# main.net
KiCad netlist of a schematic drawn in Altium Designer
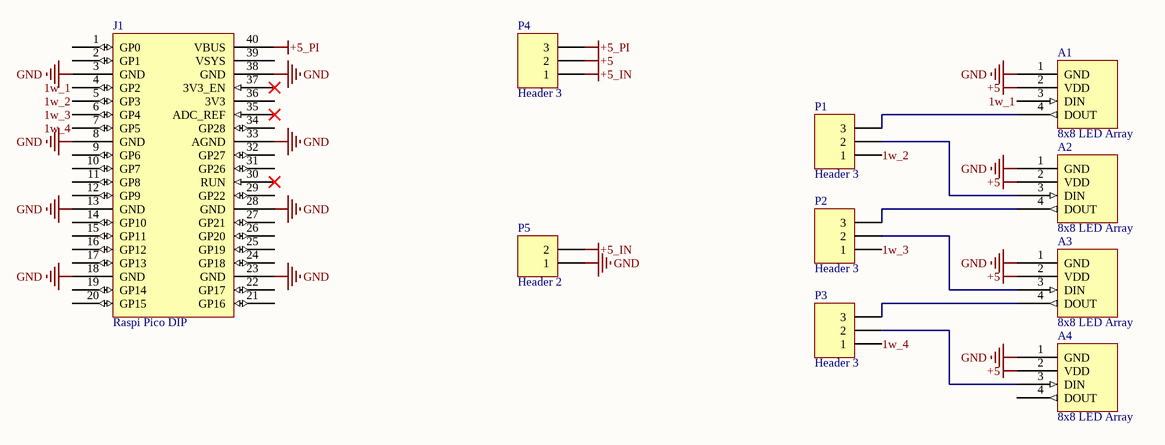
[diagram p0: main.SchDoc]

(export (version "E")
  (design (tool "Eeschema 10.0.6"))
  (components
    (comp (ref "A1")
      (value "8x8 LED Array")
      (footprint "12x12 SK6805 Matrix")
      (libsource (lib "SchmittLib") (part "12x12 SK6805 Array"))
    )
    (comp (ref "A2")
      (value "8x8 LED Array")
      (footprint "12x12 SK6805 Matrix")
      (libsource (lib "SchmittLib") (part "12x12 SK6805 Array"))
    )
    (comp (ref "A3")
      (value "8x8 LED Array")
      (footprint "12x12 SK6805 Matrix")
      (libsource (lib "SchmittLib") (part "12x12 SK6805 Array"))
    )
    (comp (ref "A4")
      (value "8x8 LED Array")
      (footprint "12x12 SK6805 Matrix")
      (libsource (lib "SchmittLib") (part "12x12 SK6805 Array"))
    )
    (comp (ref "J1")
      (value "Raspi Pico DIP")
      (footprint "Raspi Pico DIP")
      (libsource (lib "SchmittLib") (part "Raspi Pico DIP"))
    )
    (comp (ref "P1")
      (value "Header 3")
      (footprint "HDR1X3")
      (description "Header, 3-Pin")
      (fields (field (name "PUBLISHER") "Altium Limited"))
      (libsource (lib "Miscellaneous Connectors") (part "Header 3"))
    )
    (comp (ref "P2")
      (value "Header 3")
      (footprint "HDR1X3")
      (description "Header, 3-Pin")
      (fields (field (name "PUBLISHER") "Altium Limited"))
      (libsource (lib "Miscellaneous Connectors") (part "Header 3"))
    )
    (comp (ref "P3")
      (value "Header 3")
      (footprint "HDR1X3")
      (description "Header, 3-Pin")
      (fields (field (name "PUBLISHER") "Altium Limited"))
      (libsource (lib "Miscellaneous Connectors") (part "Header 3"))
    )
    (comp (ref "P4")
      (value "Header 3")
      (footprint "HDR1X3")
      (description "Header, 3-Pin")
      (fields (field (name "PUBLISHER") "Altium Limited"))
      (libsource (lib "Miscellaneous Connectors") (part "Header 3"))
    )
    (comp (ref "P5")
      (value "Header 2")
      (footprint "HDR1X2")
      (description "Header, 2-Pin")
      (fields (field (name "PUBLISHER") "Altium Limited"))
      (libsource (lib "Miscellaneous Connectors") (part "Header 2"))
    )
  )
  (nets
    (net (code "1") (name "+5") (class "Default")
      (node (ref "A1") (pin "2") (pinfunction "VDD_2") (pintype "power_in"))
      (node (ref "A2") (pin "2") (pinfunction "VDD_2") (pintype "power_in"))
      (node (ref "A3") (pin "2") (pinfunction "VDD_2") (pintype "power_in"))
      (node (ref "A4") (pin "2") (pinfunction "VDD_2") (pintype "power_in"))
      (node (ref "P4") (pin "2") (pinfunction "2_2") (pintype "passive"))
    )
    (net (code "2") (name "+5_IN") (class "Default")
      (node (ref "P4") (pin "1") (pinfunction "1_1") (pintype "passive"))
      (node (ref "P5") (pin "2") (pinfunction "2_2") (pintype "passive"))
    )
    (net (code "3") (name "+5_PI") (class "Default")
      (node (ref "J1") (pin "40") (pinfunction "VBUS_40") (pintype "power_in"))
      (node (ref "P4") (pin "3") (pinfunction "3_3") (pintype "passive"))
    )
    (net (code "4") (name "/1w_1") (class "Default")
      (node (ref "A1") (pin "3") (pinfunction "DIN_3") (pintype "input"))
      (node (ref "J1") (pin "4") (pinfunction "GP2_4") (pintype "bidirectional"))
    )
    (net (code "5") (name "/1w_2") (class "Default")
      (node (ref "J1") (pin "5") (pinfunction "GP3_5") (pintype "bidirectional"))
      (node (ref "P1") (pin "1") (pinfunction "1_1") (pintype "passive"))
    )
    (net (code "6") (name "/1w_3") (class "Default")
      (node (ref "J1") (pin "6") (pinfunction "GP4_6") (pintype "bidirectional"))
      (node (ref "P2") (pin "1") (pinfunction "1_1") (pintype "passive"))
    )
    (net (code "7") (name "/1w_4") (class "Default")
      (node (ref "J1") (pin "7") (pinfunction "GP5_7") (pintype "bidirectional"))
      (node (ref "P3") (pin "1") (pinfunction "1_1") (pintype "passive"))
    )
    (net (code "8") (name "GND") (class "Default")
      (node (ref "A1") (pin "1") (pinfunction "GND_1") (pintype "power_in"))
      (node (ref "A2") (pin "1") (pinfunction "GND_1") (pintype "power_in"))
      (node (ref "A3") (pin "1") (pinfunction "GND_1") (pintype "power_in"))
      (node (ref "A4") (pin "1") (pinfunction "GND_1") (pintype "power_in"))
      (node (ref "J1") (pin "13") (pinfunction "GND_13") (pintype "power_in"))
      (node (ref "J1") (pin "18") (pinfunction "GND_18") (pintype "power_in"))
      (node (ref "J1") (pin "23") (pinfunction "GND_23") (pintype "power_in"))
      (node (ref "J1") (pin "28") (pinfunction "GND_28") (pintype "power_in"))
      (node (ref "J1") (pin "3") (pinfunction "GND_3") (pintype "power_in"))
      (node (ref "J1") (pin "33") (pinfunction "AGND_33") (pintype "power_in"))
      (node (ref "J1") (pin "38") (pinfunction "GND_38") (pintype "power_in"))
      (node (ref "J1") (pin "8") (pinfunction "GND_8") (pintype "power_in"))
      (node (ref "P5") (pin "1") (pinfunction "1_1") (pintype "passive"))
    )
    (net (code "9") (name "Net-(A1-DOUT)") (class "Default")
      (node (ref "A1") (pin "4") (pinfunction "DOUT_4") (pintype "output"))
      (node (ref "P1") (pin "3") (pinfunction "3_3") (pintype "passive"))
    )
    (net (code "10") (name "Net-(A2-DIN)") (class "Default")
      (node (ref "A2") (pin "3") (pinfunction "DIN_3") (pintype "input"))
      (node (ref "P1") (pin "2") (pinfunction "2_2") (pintype "passive"))
    )
    (net (code "11") (name "Net-(A2-DOUT)") (class "Default")
      (node (ref "A2") (pin "4") (pinfunction "DOUT_4") (pintype "output"))
      (node (ref "P2") (pin "3") (pinfunction "3_3") (pintype "passive"))
    )
    (net (code "12") (name "Net-(A3-DIN)") (class "Default")
      (node (ref "A3") (pin "3") (pinfunction "DIN_3") (pintype "input"))
      (node (ref "P2") (pin "2") (pinfunction "2_2") (pintype "passive"))
    )
    (net (code "13") (name "Net-(A3-DOUT)") (class "Default")
      (node (ref "A3") (pin "4") (pinfunction "DOUT_4") (pintype "output"))
      (node (ref "P3") (pin "3") (pinfunction "3_3") (pintype "passive"))
    )
    (net (code "14") (name "Net-(A4-DIN)") (class "Default")
      (node (ref "A4") (pin "3") (pinfunction "DIN_3") (pintype "input"))
      (node (ref "P3") (pin "2") (pinfunction "2_2") (pintype "passive"))
    )
    (net (code "15") (name "unconnected-(A4-DOUT-Pad4)") (class "Default")
      (node (ref "A4") (pin "4") (pinfunction "DOUT_4") (pintype "output"))
    )
    (net (code "16") (name "unconnected-(J1-3V3-Pad36)") (class "Default")
      (node (ref "J1") (pin "36") (pinfunction "3V3_36") (pintype "power_in"))
    )
    (net (code "17") (name "unconnected-(J1-3V3_EN-Pad37)") (class "Default")
      (node (ref "J1") (pin "37") (pinfunction "3V3_EN_37") (pintype "input+no_connect"))
    )
    (net (code "18") (name "unconnected-(J1-ADC_REF-Pad35)") (class "Default")
      (node (ref "J1") (pin "35") (pinfunction "ADC_REF_35") (pintype "input+no_connect"))
    )
    (net (code "19") (name "unconnected-(J1-GP0-Pad1)") (class "Default")
      (node (ref "J1") (pin "1") (pinfunction "GP0_1") (pintype "bidirectional"))
    )
    (net (code "20") (name "unconnected-(J1-GP1-Pad2)") (class "Default")
      (node (ref "J1") (pin "2") (pinfunction "GP1_2") (pintype "bidirectional"))
    )
    (net (code "21") (name "unconnected-(J1-GP6-Pad9)") (class "Default")
      (node (ref "J1") (pin "9") (pinfunction "GP6_9") (pintype "bidirectional"))
    )
    (net (code "22") (name "unconnected-(J1-GP7-Pad10)") (class "Default")
      (node (ref "J1") (pin "10") (pinfunction "GP7_10") (pintype "bidirectional"))
    )
    (net (code "23") (name "unconnected-(J1-GP8-Pad11)") (class "Default")
      (node (ref "J1") (pin "11") (pinfunction "GP8_11") (pintype "bidirectional"))
    )
    (net (code "24") (name "unconnected-(J1-GP9-Pad12)") (class "Default")
      (node (ref "J1") (pin "12") (pinfunction "GP9_12") (pintype "bidirectional"))
    )
    (net (code "25") (name "unconnected-(J1-GP10-Pad14)") (class "Default")
      (node (ref "J1") (pin "14") (pinfunction "GP10_14") (pintype "bidirectional"))
    )
    (net (code "26") (name "unconnected-(J1-GP11-Pad15)") (class "Default")
      (node (ref "J1") (pin "15") (pinfunction "GP11_15") (pintype "bidirectional"))
    )
    (net (code "27") (name "unconnected-(J1-GP12-Pad16)") (class "Default")
      (node (ref "J1") (pin "16") (pinfunction "GP12_16") (pintype "bidirectional"))
    )
    (net (code "28") (name "unconnected-(J1-GP13-Pad17)") (class "Default")
      (node (ref "J1") (pin "17") (pinfunction "GP13_17") (pintype "bidirectional"))
    )
    (net (code "29") (name "unconnected-(J1-GP14-Pad19)") (class "Default")
      (node (ref "J1") (pin "19") (pinfunction "GP14_19") (pintype "bidirectional"))
    )
    (net (code "30") (name "unconnected-(J1-GP15-Pad20)") (class "Default")
      (node (ref "J1") (pin "20") (pinfunction "GP15_20") (pintype "bidirectional"))
    )
    (net (code "31") (name "unconnected-(J1-GP16-Pad21)") (class "Default")
      (node (ref "J1") (pin "21") (pinfunction "GP16_21") (pintype "bidirectional"))
    )
    (net (code "32") (name "unconnected-(J1-GP17-Pad22)") (class "Default")
      (node (ref "J1") (pin "22") (pinfunction "GP17_22") (pintype "bidirectional"))
    )
    (net (code "33") (name "unconnected-(J1-GP18-Pad24)") (class "Default")
      (node (ref "J1") (pin "24") (pinfunction "GP18_24") (pintype "bidirectional"))
    )
    (net (code "34") (name "unconnected-(J1-GP19-Pad25)") (class "Default")
      (node (ref "J1") (pin "25") (pinfunction "GP19_25") (pintype "bidirectional"))
    )
    (net (code "35") (name "unconnected-(J1-GP20-Pad26)") (class "Default")
      (node (ref "J1") (pin "26") (pinfunction "GP20_26") (pintype "bidirectional"))
    )
    (net (code "36") (name "unconnected-(J1-GP21-Pad27)") (class "Default")
      (node (ref "J1") (pin "27") (pinfunction "GP21_27") (pintype "bidirectional"))
    )
    (net (code "37") (name "unconnected-(J1-GP22-Pad29)") (class "Default")
      (node (ref "J1") (pin "29") (pinfunction "GP22_29") (pintype "bidirectional"))
    )
    (net (code "38") (name "unconnected-(J1-GP26-Pad31)") (class "Default")
      (node (ref "J1") (pin "31") (pinfunction "GP26_31") (pintype "bidirectional"))
    )
    (net (code "39") (name "unconnected-(J1-GP27-Pad32)") (class "Default")
      (node (ref "J1") (pin "32") (pinfunction "GP27_32") (pintype "bidirectional"))
    )
    (net (code "40") (name "unconnected-(J1-GP28-Pad34)") (class "Default")
      (node (ref "J1") (pin "34") (pinfunction "GP28_34") (pintype "bidirectional"))
    )
    (net (code "41") (name "unconnected-(J1-RUN-Pad30)") (class "Default")
      (node (ref "J1") (pin "30") (pinfunction "RUN_30") (pintype "input+no_connect"))
    )
    (net (code "42") (name "unconnected-(J1-VSYS-Pad39)") (class "Default")
      (node (ref "J1") (pin "39") (pinfunction "VSYS_39") (pintype "power_in"))
    )
  )
)
